# mcp3008_rpi_new.net
KiCad netlist of a schematic drawn in EAGLE
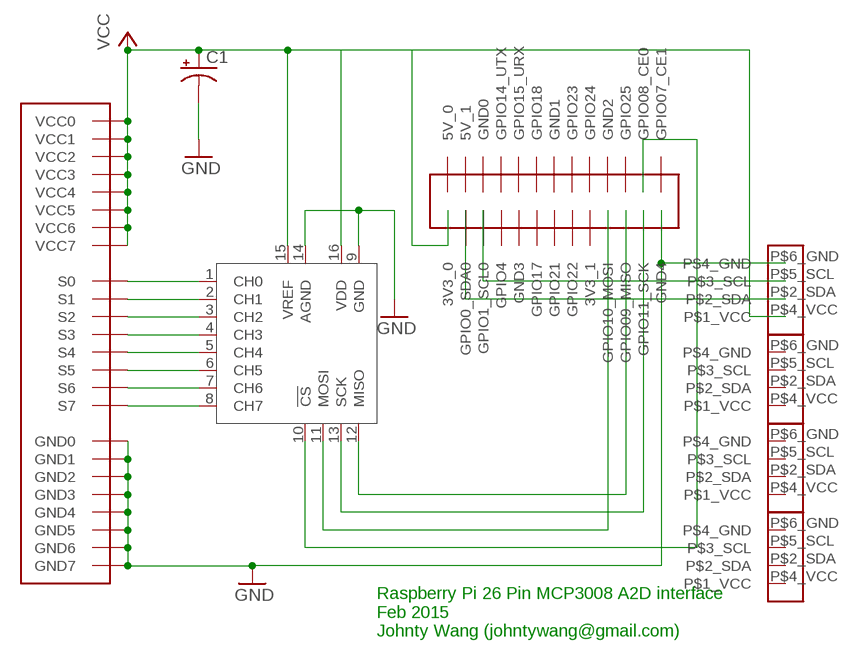
[diagram p0: schematic, sheet 1]

(export (version "E")
  (design (tool "Eeschema 10.0.6"))
  (components
    (comp (ref "C1")
      (value "CPOL-USE2.5-6")
      (footprint "eagle-import:E2,5-6")
      (libsource (lib "eagle-import") (part "CPOL-USE2.5-6"))
    )
    (comp (ref "U$1")
      (value "3BY83X8_SAMTEC")
      (footprint "eagle-import:3X8_PKG")
      (libsource (lib "eagle-import") (part "3BY83X8_SAMTEC"))
    )
    (comp (ref "U$2")
      (value "RPI_26")
      (footprint "eagle-import:RPI26")
      (libsource (lib "eagle-import") (part "RPI_26"))
    )
    (comp (ref "U$3")
      (value "MCP3008P")
      (footprint "eagle-import:DIL16")
      (libsource (lib "eagle-import") (part "MCP3008P"))
    )
    (comp (ref "U$4")
      (value "ICUBE_I2C")
      (footprint "eagle-import:2X3")
      (libsource (lib "eagle-import") (part "ICUBE_I2C"))
    )
    (comp (ref "U$5")
      (value "ICUBE_I2C")
      (footprint "eagle-import:2X3")
      (libsource (lib "eagle-import") (part "ICUBE_I2C"))
    )
    (comp (ref "U$6")
      (value "ICUBE_I2C")
      (footprint "eagle-import:2X3")
      (libsource (lib "eagle-import") (part "ICUBE_I2C"))
    )
    (comp (ref "U$7")
      (value "ICUBE_I2C")
      (footprint "eagle-import:2X3")
      (libsource (lib "eagle-import") (part "ICUBE_I2C"))
    )
  )
  (nets
    (net (code "1") (name "/5V_0") (class "Default")
      (node (ref "U$2") (pin "5V0") (pinfunction "5V_0_5V0") (pintype "power_in"))
    )
    (net (code "2") (name "GND") (class "Default")
      (node (ref "C1") (pin "-") (pinfunction "-_-") (pintype "passive"))
      (node (ref "U$1") (pin "GND0") (pinfunction "GND0_GND0") (pintype "bidirectional"))
      (node (ref "U$1") (pin "GND1") (pinfunction "GND1_GND1") (pintype "bidirectional"))
      (node (ref "U$1") (pin "GND2") (pinfunction "GND2_GND2") (pintype "bidirectional"))
      (node (ref "U$1") (pin "GND3") (pinfunction "GND3_GND3") (pintype "bidirectional"))
      (node (ref "U$1") (pin "GND4") (pinfunction "GND4_GND4") (pintype "bidirectional"))
      (node (ref "U$1") (pin "GND5") (pinfunction "GND5_GND5") (pintype "bidirectional"))
      (node (ref "U$1") (pin "GND6") (pinfunction "GND6_GND6") (pintype "bidirectional"))
      (node (ref "U$1") (pin "GND7") (pinfunction "GND7_GND7") (pintype "bidirectional"))
      (node (ref "U$2") (pin "GND4") (pinfunction "GND4_GND4") (pintype "bidirectional"))
      (node (ref "U$3") (pin "14") (pinfunction "AGND_14") (pintype "power_in"))
      (node (ref "U$3") (pin "9") (pinfunction "GND_9") (pintype "power_in"))
      (node (ref "U$4") (pin "P$6_GND") (pinfunction "P$4_GND_P$6_GND") (pintype "bidirectional"))
    )
    (net (code "3") (name "Net-(U$2-GPIO0_SDA0)") (class "Default")
      (node (ref "U$2") (pin "GPIO0") (pinfunction "GPIO0_SDA0_GPIO0") (pintype "bidirectional"))
      (node (ref "U$4") (pin "P$2_SDA") (pinfunction "P$2_SDA_P$2_SDA") (pintype "bidirectional"))
    )
    (net (code "4") (name "Net-(U$2-GPIO1_SCL0)") (class "Default")
      (node (ref "U$2") (pin "GPIO01") (pinfunction "GPIO1_SCL0_GPIO01") (pintype "bidirectional"))
      (node (ref "U$4") (pin "P$5_SCL") (pinfunction "P$3_SCL_P$5_SCL") (pintype "bidirectional"))
    )
    (net (code "5") (name "Net-(U$2-GPIO08_CE0)") (class "Default")
      (node (ref "U$2") (pin "GPIO08") (pinfunction "GPIO08_CE0_GPIO08") (pintype "bidirectional"))
      (node (ref "U$3") (pin "10") (pinfunction "~{CS}_10") (pintype "input"))
    )
    (net (code "6") (name "Net-(U$2-GPIO09_MISO)") (class "Default")
      (node (ref "U$2") (pin "GPIO09") (pinfunction "GPIO09_MISO_GPIO09") (pintype "bidirectional"))
      (node (ref "U$3") (pin "12") (pinfunction "MISO_12") (pintype "output"))
    )
    (net (code "7") (name "Net-(U$2-GPIO10_MOSI)") (class "Default")
      (node (ref "U$2") (pin "GPIO10") (pinfunction "GPIO10_MOSI_GPIO10") (pintype "bidirectional"))
      (node (ref "U$3") (pin "11") (pinfunction "MOSI_11") (pintype "input"))
    )
    (net (code "8") (name "Net-(U$2-GPIO11_SCK)") (class "Default")
      (node (ref "U$2") (pin "GPIO11") (pinfunction "GPIO11_SCK_GPIO11") (pintype "bidirectional"))
      (node (ref "U$3") (pin "13") (pinfunction "SCK_13") (pintype "input"))
    )
    (net (code "9") (name "Net-(U$3-CH0)") (class "Default")
      (node (ref "U$1") (pin "S0") (pinfunction "S0_S0") (pintype "bidirectional"))
      (node (ref "U$3") (pin "1") (pinfunction "CH0_1") (pintype "input"))
    )
    (net (code "10") (name "Net-(U$3-CH1)") (class "Default")
      (node (ref "U$1") (pin "S1") (pinfunction "S1_S1") (pintype "bidirectional"))
      (node (ref "U$3") (pin "2") (pinfunction "CH1_2") (pintype "input"))
    )
    (net (code "11") (name "Net-(U$3-CH2)") (class "Default")
      (node (ref "U$1") (pin "S2") (pinfunction "S2_S2") (pintype "bidirectional"))
      (node (ref "U$3") (pin "3") (pinfunction "CH2_3") (pintype "input"))
    )
    (net (code "12") (name "Net-(U$3-CH3)") (class "Default")
      (node (ref "U$1") (pin "S3") (pinfunction "S3_S3") (pintype "bidirectional"))
      (node (ref "U$3") (pin "4") (pinfunction "CH3_4") (pintype "input"))
    )
    (net (code "13") (name "Net-(U$3-CH4)") (class "Default")
      (node (ref "U$1") (pin "S4") (pinfunction "S4_S4") (pintype "bidirectional"))
      (node (ref "U$3") (pin "5") (pinfunction "CH4_5") (pintype "input"))
    )
    (net (code "14") (name "Net-(U$3-CH5)") (class "Default")
      (node (ref "U$1") (pin "S5") (pinfunction "S5_S5") (pintype "bidirectional"))
      (node (ref "U$3") (pin "6") (pinfunction "CH5_6") (pintype "input"))
    )
    (net (code "15") (name "Net-(U$3-CH6)") (class "Default")
      (node (ref "U$1") (pin "S6") (pinfunction "S6_S6") (pintype "bidirectional"))
      (node (ref "U$3") (pin "7") (pinfunction "CH6_7") (pintype "input"))
    )
    (net (code "16") (name "Net-(U$3-CH7)") (class "Default")
      (node (ref "U$1") (pin "S7") (pinfunction "S7_S7") (pintype "bidirectional"))
      (node (ref "U$3") (pin "8") (pinfunction "CH7_8") (pintype "input"))
    )
    (net (code "17") (name "VCC") (class "Default")
      (node (ref "C1") (pin "+") (pinfunction "+_+") (pintype "passive"))
      (node (ref "U$1") (pin "VCC0") (pinfunction "VCC0_VCC0") (pintype "bidirectional"))
      (node (ref "U$1") (pin "VCC1") (pinfunction "VCC1_VCC1") (pintype "bidirectional"))
      (node (ref "U$1") (pin "VCC2") (pinfunction "VCC2_VCC2") (pintype "bidirectional"))
      (node (ref "U$1") (pin "VCC3") (pinfunction "VCC3_VCC3") (pintype "bidirectional"))
      (node (ref "U$1") (pin "VCC4") (pinfunction "VCC4_VCC4") (pintype "bidirectional"))
      (node (ref "U$1") (pin "VCC5") (pinfunction "VCC5_VCC5") (pintype "bidirectional"))
      (node (ref "U$1") (pin "VCC6") (pinfunction "VCC6_VCC6") (pintype "bidirectional"))
      (node (ref "U$1") (pin "VCC7") (pinfunction "VCC7_VCC7") (pintype "bidirectional"))
      (node (ref "U$2") (pin "3V3_0") (pinfunction "3V3_0_3V3_0") (pintype "bidirectional"))
      (node (ref "U$3") (pin "15") (pinfunction "VREF_15") (pintype "power_in"))
      (node (ref "U$3") (pin "16") (pinfunction "VDD_16") (pintype "power_in"))
      (node (ref "U$4") (pin "P$4_VCC") (pinfunction "P$1_VCC_P$4_VCC") (pintype "bidirectional"))
    )
    (net (code "18") (name "unconnected-(U$2-5V_1-Pad5V1)") (class "Default")
      (node (ref "U$2") (pin "5V1") (pinfunction "5V_1_5V1") (pintype "bidirectional"))
    )
    (net (code "19") (name "unconnected-(U$2-GPIO4-PadGPIO04)") (class "Default")
      (node (ref "U$2") (pin "GPIO04") (pinfunction "GPIO4_GPIO04") (pintype "bidirectional"))
    )
    (net (code "20") (name "unconnected-(U$2-GPIO07_CE1-PadGPIO07)") (class "Default")
      (node (ref "U$2") (pin "GPIO07") (pinfunction "GPIO07_CE1_GPIO07") (pintype "bidirectional"))
    )
    (net (code "21") (name "unconnected-(U$2-GPIO14_UTX-PadGPIO14)") (class "Default")
      (node (ref "U$2") (pin "GPIO14") (pinfunction "GPIO14_UTX_GPIO14") (pintype "bidirectional"))
    )
    (net (code "22") (name "unconnected-(U$2-GPIO15_URX-PadGPIO15)") (class "Default")
      (node (ref "U$2") (pin "GPIO15") (pinfunction "GPIO15_URX_GPIO15") (pintype "bidirectional"))
    )
    (net (code "23") (name "unconnected-(U$2-Pad3V3_1)") (class "Default")
      (node (ref "U$2") (pin "3V3_1") (pinfunction "3V3_1_3V3_1") (pintype "bidirectional"))
    )
    (net (code "24") (name "unconnected-(U$2-PadGND0)") (class "Default")
      (node (ref "U$2") (pin "GND0") (pinfunction "GND0_GND0") (pintype "bidirectional"))
    )
    (net (code "25") (name "unconnected-(U$2-PadGND1)") (class "Default")
      (node (ref "U$2") (pin "GND1") (pinfunction "GND1_GND1") (pintype "bidirectional"))
    )
    (net (code "26") (name "unconnected-(U$2-PadGND2)") (class "Default")
      (node (ref "U$2") (pin "GND2") (pinfunction "GND2_GND2") (pintype "bidirectional"))
    )
    (net (code "27") (name "unconnected-(U$2-PadGND3)") (class "Default")
      (node (ref "U$2") (pin "GND3") (pinfunction "GND3_GND3") (pintype "bidirectional"))
    )
    (net (code "28") (name "unconnected-(U$2-PadGPIO17)") (class "Default")
      (node (ref "U$2") (pin "GPIO17") (pinfunction "GPIO17_GPIO17") (pintype "bidirectional"))
    )
    (net (code "29") (name "unconnected-(U$2-PadGPIO18)") (class "Default")
      (node (ref "U$2") (pin "GPIO18") (pinfunction "GPIO18_GPIO18") (pintype "bidirectional"))
    )
    (net (code "30") (name "unconnected-(U$2-PadGPIO21)") (class "Default")
      (node (ref "U$2") (pin "GPIO21") (pinfunction "GPIO21_GPIO21") (pintype "bidirectional"))
    )
    (net (code "31") (name "unconnected-(U$2-PadGPIO22)") (class "Default")
      (node (ref "U$2") (pin "GPIO22") (pinfunction "GPIO22_GPIO22") (pintype "bidirectional"))
    )
    (net (code "32") (name "unconnected-(U$2-PadGPIO23)") (class "Default")
      (node (ref "U$2") (pin "GPIO23") (pinfunction "GPIO23_GPIO23") (pintype "bidirectional"))
    )
    (net (code "33") (name "unconnected-(U$2-PadGPIO24)") (class "Default")
      (node (ref "U$2") (pin "GPIO24") (pinfunction "GPIO24_GPIO24") (pintype "bidirectional"))
    )
    (net (code "34") (name "unconnected-(U$2-PadGPIO25)") (class "Default")
      (node (ref "U$2") (pin "GPIO25") (pinfunction "GPIO25_GPIO25") (pintype "bidirectional"))
    )
    (net (code "35") (name "unconnected-(U$5-P$1_VCC-PadP$4_VCC)") (class "Default")
      (node (ref "U$5") (pin "P$4_VCC") (pinfunction "P$1_VCC_P$4_VCC") (pintype "bidirectional"))
    )
    (net (code "36") (name "unconnected-(U$5-P$3_SCL-PadP$5_SCL)") (class "Default")
      (node (ref "U$5") (pin "P$5_SCL") (pinfunction "P$3_SCL_P$5_SCL") (pintype "bidirectional"))
    )
    (net (code "37") (name "unconnected-(U$5-P$4_GND-PadP$6_GND)") (class "Default")
      (node (ref "U$5") (pin "P$6_GND") (pinfunction "P$4_GND_P$6_GND") (pintype "bidirectional"))
    )
    (net (code "38") (name "unconnected-(U$5-PadP$2_SDA)") (class "Default")
      (node (ref "U$5") (pin "P$2_SDA") (pinfunction "P$2_SDA_P$2_SDA") (pintype "bidirectional"))
    )
    (net (code "39") (name "unconnected-(U$6-P$1_VCC-PadP$4_VCC)") (class "Default")
      (node (ref "U$6") (pin "P$4_VCC") (pinfunction "P$1_VCC_P$4_VCC") (pintype "bidirectional"))
    )
    (net (code "40") (name "unconnected-(U$6-P$3_SCL-PadP$5_SCL)") (class "Default")
      (node (ref "U$6") (pin "P$5_SCL") (pinfunction "P$3_SCL_P$5_SCL") (pintype "bidirectional"))
    )
    (net (code "41") (name "unconnected-(U$6-P$4_GND-PadP$6_GND)") (class "Default")
      (node (ref "U$6") (pin "P$6_GND") (pinfunction "P$4_GND_P$6_GND") (pintype "bidirectional"))
    )
    (net (code "42") (name "unconnected-(U$6-PadP$2_SDA)") (class "Default")
      (node (ref "U$6") (pin "P$2_SDA") (pinfunction "P$2_SDA_P$2_SDA") (pintype "bidirectional"))
    )
    (net (code "43") (name "unconnected-(U$7-P$1_VCC-PadP$4_VCC)") (class "Default")
      (node (ref "U$7") (pin "P$4_VCC") (pinfunction "P$1_VCC_P$4_VCC") (pintype "bidirectional"))
    )
    (net (code "44") (name "unconnected-(U$7-P$3_SCL-PadP$5_SCL)") (class "Default")
      (node (ref "U$7") (pin "P$5_SCL") (pinfunction "P$3_SCL_P$5_SCL") (pintype "bidirectional"))
    )
    (net (code "45") (name "unconnected-(U$7-P$4_GND-PadP$6_GND)") (class "Default")
      (node (ref "U$7") (pin "P$6_GND") (pinfunction "P$4_GND_P$6_GND") (pintype "bidirectional"))
    )
    (net (code "46") (name "unconnected-(U$7-PadP$2_SDA)") (class "Default")
      (node (ref "U$7") (pin "P$2_SDA") (pinfunction "P$2_SDA_P$2_SDA") (pintype "bidirectional"))
    )
  )
)
